# Nixie_Roehren-IN12b-V1_2.net
KiCad netlist of a schematic drawn in EAGLE
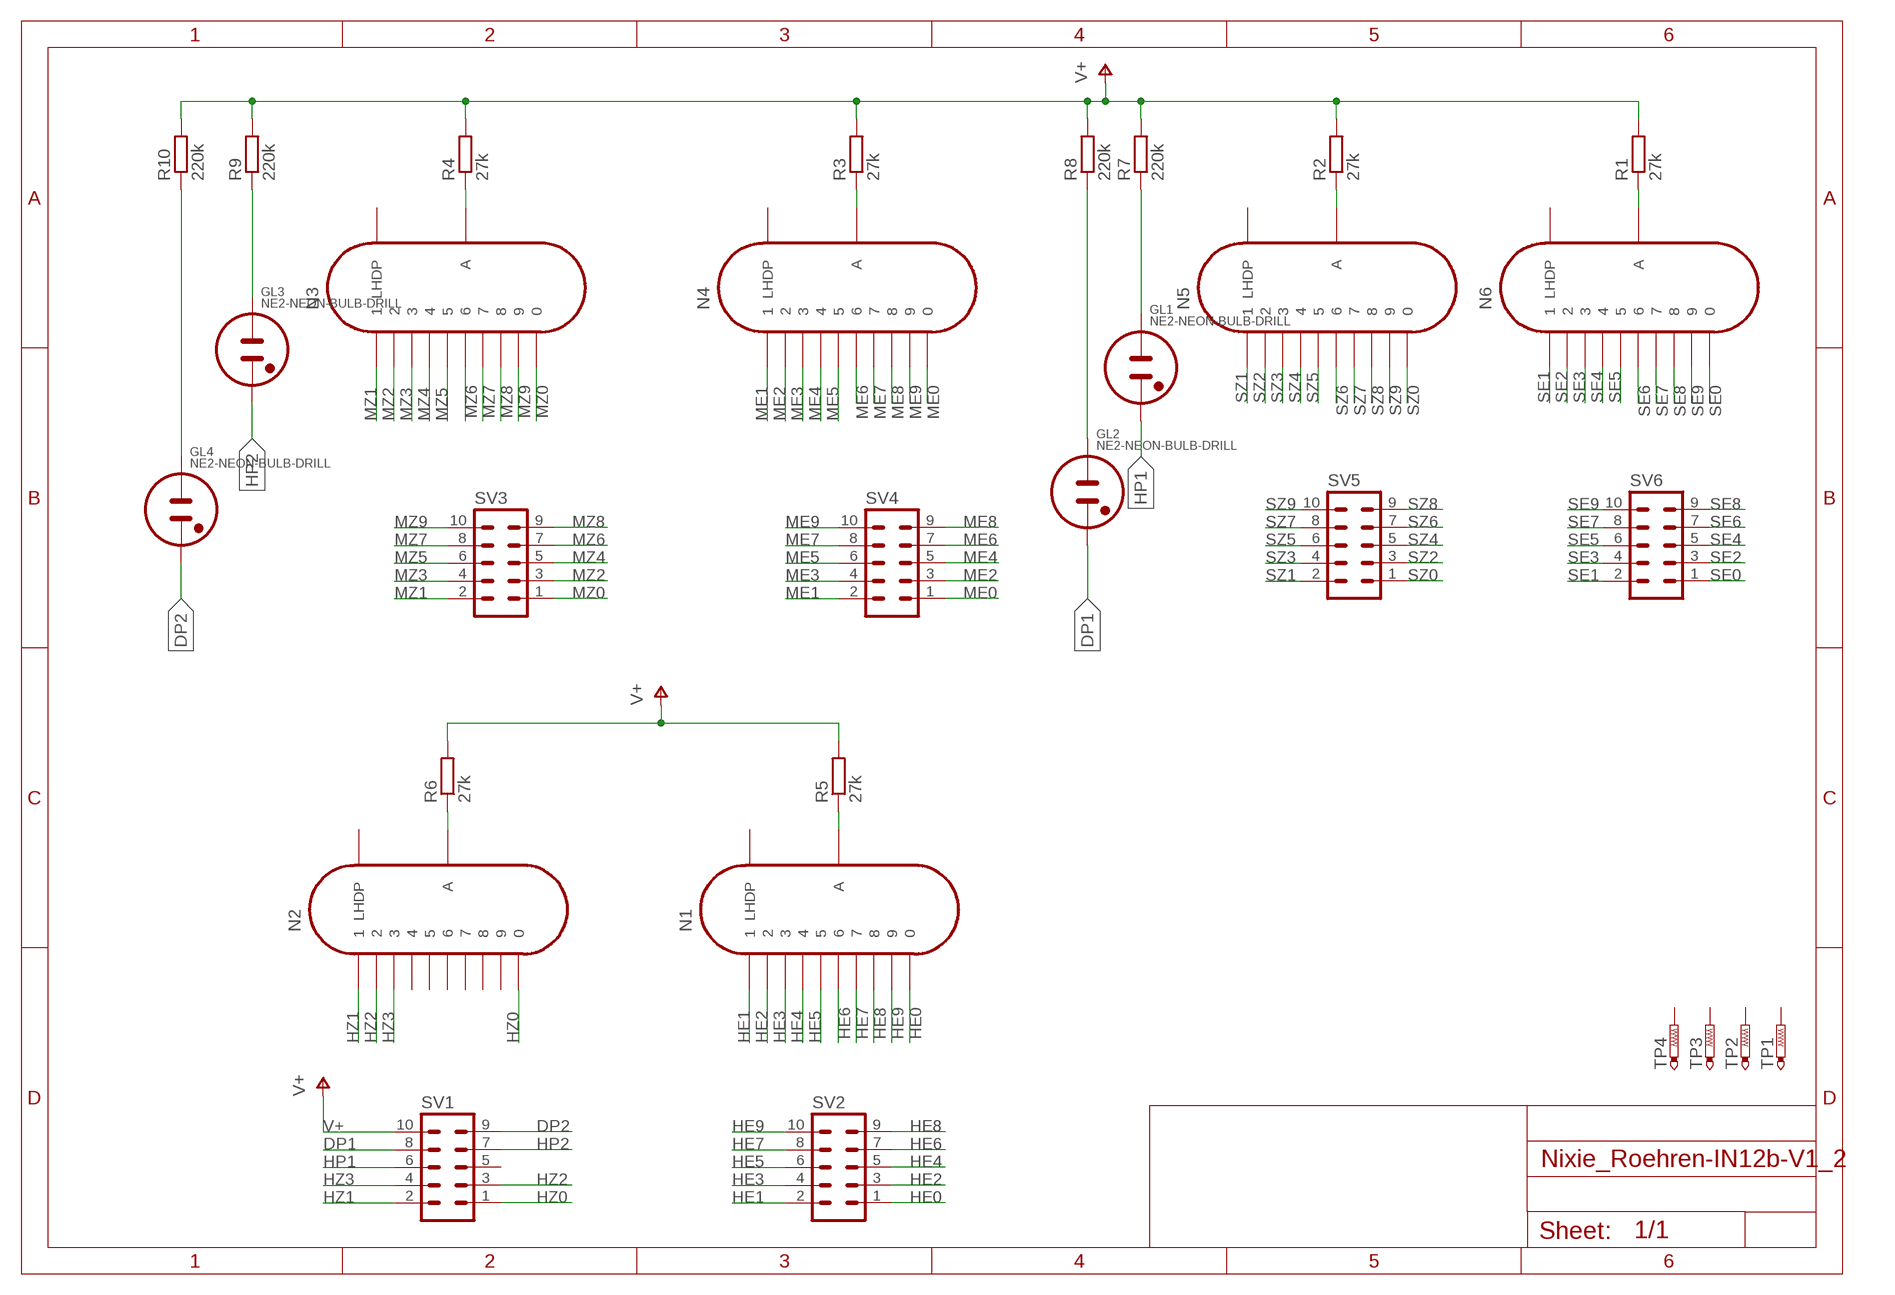
[diagram p0: schematic, sheet 1]

(export (version "E")
  (design (tool "Eeschema 10.0.6"))
  (components
    (comp (ref "GL1")
      (value "NE2-NEON-BULB-DRILL")
      (footprint "eagle-import:NE2-NEON-BULB-DRILL")
      (libsource (lib "eagle-import") (part "NE2-NEON-BULB-DRILL"))
    )
    (comp (ref "GL2")
      (value "NE2-NEON-BULB-DRILL")
      (footprint "eagle-import:NE2-NEON-BULB-DRILL")
      (libsource (lib "eagle-import") (part "NE2-NEON-BULB-DRILL"))
    )
    (comp (ref "GL3")
      (value "NE2-NEON-BULB-DRILL")
      (footprint "eagle-import:NE2-NEON-BULB-DRILL")
      (libsource (lib "eagle-import") (part "NE2-NEON-BULB-DRILL"))
    )
    (comp (ref "GL4")
      (value "NE2-NEON-BULB-DRILL")
      (footprint "eagle-import:NE2-NEON-BULB-DRILL")
      (libsource (lib "eagle-import") (part "NE2-NEON-BULB-DRILL"))
    )
    (comp (ref "N1")
      (value "IN-12B")
      (footprint "eagle-import:IN-12")
      (libsource (lib "eagle-import") (part "IN-12B"))
    )
    (comp (ref "N2")
      (value "IN-12B")
      (footprint "eagle-import:IN-12")
      (libsource (lib "eagle-import") (part "IN-12B"))
    )
    (comp (ref "N3")
      (value "IN-12B")
      (footprint "eagle-import:IN-12")
      (libsource (lib "eagle-import") (part "IN-12B"))
    )
    (comp (ref "N4")
      (value "IN-12B")
      (footprint "eagle-import:IN-12")
      (libsource (lib "eagle-import") (part "IN-12B"))
    )
    (comp (ref "N5")
      (value "IN-12B")
      (footprint "eagle-import:IN-12")
      (libsource (lib "eagle-import") (part "IN-12B"))
    )
    (comp (ref "N6")
      (value "IN-12B")
      (footprint "eagle-import:IN-12")
      (libsource (lib "eagle-import") (part "IN-12B"))
    )
    (comp (ref "R1")
      (value "27k")
      (footprint "eagle-import:0207_10")
      (libsource (lib "eagle-import") (part "R-EU_0207/10"))
    )
    (comp (ref "R2")
      (value "27k")
      (footprint "eagle-import:0207_10")
      (libsource (lib "eagle-import") (part "R-EU_0207/10"))
    )
    (comp (ref "R3")
      (value "27k")
      (footprint "eagle-import:0207_10")
      (libsource (lib "eagle-import") (part "R-EU_0207/10"))
    )
    (comp (ref "R4")
      (value "27k")
      (footprint "eagle-import:0207_10")
      (libsource (lib "eagle-import") (part "R-EU_0207/10"))
    )
    (comp (ref "R5")
      (value "27k")
      (footprint "eagle-import:0207_10")
      (libsource (lib "eagle-import") (part "R-EU_0207/10"))
    )
    (comp (ref "R6")
      (value "27k")
      (footprint "eagle-import:0207_10")
      (libsource (lib "eagle-import") (part "R-EU_0207/10"))
    )
    (comp (ref "R7")
      (value "220k")
      (footprint "eagle-import:0207_10")
      (libsource (lib "eagle-import") (part "R-EU_0207/10"))
    )
    (comp (ref "R8")
      (value "220k")
      (footprint "eagle-import:0207_10")
      (libsource (lib "eagle-import") (part "R-EU_0207/10"))
    )
    (comp (ref "R9")
      (value "220k")
      (footprint "eagle-import:0207_10")
      (libsource (lib "eagle-import") (part "R-EU_0207/10"))
    )
    (comp (ref "R10")
      (value "220k")
      (footprint "eagle-import:0207_10")
      (libsource (lib "eagle-import") (part "R-EU_0207/10"))
    )
    (comp (ref "SV1")
      (value "ML10")
      (footprint "eagle-import:ML10")
      (libsource (lib "eagle-import") (part "ML10"))
    )
    (comp (ref "SV2")
      (value "ML10")
      (footprint "eagle-import:ML10")
      (libsource (lib "eagle-import") (part "ML10"))
    )
    (comp (ref "SV3")
      (value "ML10")
      (footprint "eagle-import:ML10")
      (libsource (lib "eagle-import") (part "ML10"))
    )
    (comp (ref "SV4")
      (value "ML10")
      (footprint "eagle-import:ML10")
      (libsource (lib "eagle-import") (part "ML10"))
    )
    (comp (ref "SV5")
      (value "ML10")
      (footprint "eagle-import:ML10")
      (libsource (lib "eagle-import") (part "ML10"))
    )
    (comp (ref "SV6")
      (value "ML10")
      (footprint "eagle-import:ML10")
      (libsource (lib "eagle-import") (part "ML10"))
    )
    (comp (ref "TP1")
      (value "PTR1B1,27")
      (footprint "eagle-import:B1,27")
      (libsource (lib "eagle-import") (part "PTR1B1,27"))
    )
    (comp (ref "TP2")
      (value "PTR1B1,27")
      (footprint "eagle-import:B1,27")
      (libsource (lib "eagle-import") (part "PTR1B1,27"))
    )
    (comp (ref "TP3")
      (value "PTR1B1,27")
      (footprint "eagle-import:B1,27")
      (libsource (lib "eagle-import") (part "PTR1B1,27"))
    )
    (comp (ref "TP4")
      (value "PTR1B1,27")
      (footprint "eagle-import:B1,27")
      (libsource (lib "eagle-import") (part "PTR1B1,27"))
    )
  )
  (nets
    (net (code "1") (name "/HE0") (class "Default")
      (node (ref "N1") (pin "0") (pinfunction "0_0") (pintype "bidirectional"))
      (node (ref "SV2") (pin "1") (pinfunction "1_1") (pintype "passive"))
    )
    (net (code "2") (name "/HE1") (class "Default")
      (node (ref "N1") (pin "1") (pinfunction "1_1") (pintype "bidirectional"))
      (node (ref "SV2") (pin "2") (pinfunction "2_2") (pintype "passive"))
    )
    (net (code "3") (name "/HE2") (class "Default")
      (node (ref "N1") (pin "2") (pinfunction "2_2") (pintype "bidirectional"))
      (node (ref "SV2") (pin "3") (pinfunction "3_3") (pintype "passive"))
    )
    (net (code "4") (name "/HE3") (class "Default")
      (node (ref "N1") (pin "3") (pinfunction "3_3") (pintype "bidirectional"))
      (node (ref "SV2") (pin "4") (pinfunction "4_4") (pintype "passive"))
    )
    (net (code "5") (name "/HE4") (class "Default")
      (node (ref "N1") (pin "4") (pinfunction "4_4") (pintype "bidirectional"))
      (node (ref "SV2") (pin "5") (pinfunction "5_5") (pintype "passive"))
    )
    (net (code "6") (name "/HE5") (class "Default")
      (node (ref "N1") (pin "5") (pinfunction "5_5") (pintype "bidirectional"))
      (node (ref "SV2") (pin "6") (pinfunction "6_6") (pintype "passive"))
    )
    (net (code "7") (name "/HE6") (class "Default")
      (node (ref "N1") (pin "6") (pinfunction "6_6") (pintype "bidirectional"))
      (node (ref "SV2") (pin "7") (pinfunction "7_7") (pintype "passive"))
    )
    (net (code "8") (name "/HE7") (class "Default")
      (node (ref "N1") (pin "7") (pinfunction "7_7") (pintype "bidirectional"))
      (node (ref "SV2") (pin "8") (pinfunction "8_8") (pintype "passive"))
    )
    (net (code "9") (name "/HE8") (class "Default")
      (node (ref "N1") (pin "8") (pinfunction "8_8") (pintype "bidirectional"))
      (node (ref "SV2") (pin "9") (pinfunction "9_9") (pintype "passive"))
    )
    (net (code "10") (name "/HE9") (class "Default")
      (node (ref "N1") (pin "9") (pinfunction "9_9") (pintype "bidirectional"))
      (node (ref "SV2") (pin "10") (pinfunction "10_10") (pintype "passive"))
    )
    (net (code "11") (name "/HZ0") (class "Default")
      (node (ref "N2") (pin "0") (pinfunction "0_0") (pintype "bidirectional"))
      (node (ref "SV1") (pin "1") (pinfunction "1_1") (pintype "passive"))
    )
    (net (code "12") (name "/HZ1") (class "Default")
      (node (ref "N2") (pin "1") (pinfunction "1_1") (pintype "bidirectional"))
      (node (ref "SV1") (pin "2") (pinfunction "2_2") (pintype "passive"))
    )
    (net (code "13") (name "/HZ2") (class "Default")
      (node (ref "N2") (pin "2") (pinfunction "2_2") (pintype "bidirectional"))
      (node (ref "SV1") (pin "3") (pinfunction "3_3") (pintype "passive"))
    )
    (net (code "14") (name "/HZ3") (class "Default")
      (node (ref "N2") (pin "3") (pinfunction "3_3") (pintype "bidirectional"))
      (node (ref "SV1") (pin "4") (pinfunction "4_4") (pintype "passive"))
    )
    (net (code "15") (name "/ME0") (class "Default")
      (node (ref "N4") (pin "0") (pinfunction "0_0") (pintype "bidirectional"))
      (node (ref "SV4") (pin "1") (pinfunction "1_1") (pintype "passive"))
    )
    (net (code "16") (name "/ME1") (class "Default")
      (node (ref "N4") (pin "1") (pinfunction "1_1") (pintype "bidirectional"))
      (node (ref "SV4") (pin "2") (pinfunction "2_2") (pintype "passive"))
    )
    (net (code "17") (name "/ME2") (class "Default")
      (node (ref "N4") (pin "2") (pinfunction "2_2") (pintype "bidirectional"))
      (node (ref "SV4") (pin "3") (pinfunction "3_3") (pintype "passive"))
    )
    (net (code "18") (name "/ME3") (class "Default")
      (node (ref "N4") (pin "3") (pinfunction "3_3") (pintype "bidirectional"))
      (node (ref "SV4") (pin "4") (pinfunction "4_4") (pintype "passive"))
    )
    (net (code "19") (name "/ME4") (class "Default")
      (node (ref "N4") (pin "4") (pinfunction "4_4") (pintype "bidirectional"))
      (node (ref "SV4") (pin "5") (pinfunction "5_5") (pintype "passive"))
    )
    (net (code "20") (name "/ME5") (class "Default")
      (node (ref "N4") (pin "5") (pinfunction "5_5") (pintype "bidirectional"))
      (node (ref "SV4") (pin "6") (pinfunction "6_6") (pintype "passive"))
    )
    (net (code "21") (name "/ME6") (class "Default")
      (node (ref "N4") (pin "6") (pinfunction "6_6") (pintype "bidirectional"))
      (node (ref "SV4") (pin "7") (pinfunction "7_7") (pintype "passive"))
    )
    (net (code "22") (name "/ME7") (class "Default")
      (node (ref "N4") (pin "7") (pinfunction "7_7") (pintype "bidirectional"))
      (node (ref "SV4") (pin "8") (pinfunction "8_8") (pintype "passive"))
    )
    (net (code "23") (name "/ME8") (class "Default")
      (node (ref "N4") (pin "8") (pinfunction "8_8") (pintype "bidirectional"))
      (node (ref "SV4") (pin "9") (pinfunction "9_9") (pintype "passive"))
    )
    (net (code "24") (name "/ME9") (class "Default")
      (node (ref "N4") (pin "9") (pinfunction "9_9") (pintype "bidirectional"))
      (node (ref "SV4") (pin "10") (pinfunction "10_10") (pintype "passive"))
    )
    (net (code "25") (name "/MZ0") (class "Default")
      (node (ref "N3") (pin "0") (pinfunction "0_0") (pintype "bidirectional"))
      (node (ref "SV3") (pin "1") (pinfunction "1_1") (pintype "passive"))
    )
    (net (code "26") (name "/MZ1") (class "Default")
      (node (ref "N3") (pin "1") (pinfunction "1_1") (pintype "bidirectional"))
      (node (ref "SV3") (pin "2") (pinfunction "2_2") (pintype "passive"))
    )
    (net (code "27") (name "/MZ2") (class "Default")
      (node (ref "N3") (pin "2") (pinfunction "2_2") (pintype "bidirectional"))
      (node (ref "SV3") (pin "3") (pinfunction "3_3") (pintype "passive"))
    )
    (net (code "28") (name "/MZ3") (class "Default")
      (node (ref "N3") (pin "3") (pinfunction "3_3") (pintype "bidirectional"))
      (node (ref "SV3") (pin "4") (pinfunction "4_4") (pintype "passive"))
    )
    (net (code "29") (name "/MZ4") (class "Default")
      (node (ref "N3") (pin "4") (pinfunction "4_4") (pintype "bidirectional"))
      (node (ref "SV3") (pin "5") (pinfunction "5_5") (pintype "passive"))
    )
    (net (code "30") (name "/MZ5") (class "Default")
      (node (ref "N3") (pin "5") (pinfunction "5_5") (pintype "bidirectional"))
      (node (ref "SV3") (pin "6") (pinfunction "6_6") (pintype "passive"))
    )
    (net (code "31") (name "/MZ6") (class "Default")
      (node (ref "N3") (pin "6") (pinfunction "6_6") (pintype "bidirectional"))
      (node (ref "SV3") (pin "7") (pinfunction "7_7") (pintype "passive"))
    )
    (net (code "32") (name "/MZ7") (class "Default")
      (node (ref "N3") (pin "7") (pinfunction "7_7") (pintype "bidirectional"))
      (node (ref "SV3") (pin "8") (pinfunction "8_8") (pintype "passive"))
    )
    (net (code "33") (name "/MZ8") (class "Default")
      (node (ref "N3") (pin "8") (pinfunction "8_8") (pintype "bidirectional"))
      (node (ref "SV3") (pin "9") (pinfunction "9_9") (pintype "passive"))
    )
    (net (code "34") (name "/MZ9") (class "Default")
      (node (ref "N3") (pin "9") (pinfunction "9_9") (pintype "bidirectional"))
      (node (ref "SV3") (pin "10") (pinfunction "10_10") (pintype "passive"))
    )
    (net (code "35") (name "/SE0") (class "Default")
      (node (ref "N6") (pin "0") (pinfunction "0_0") (pintype "bidirectional"))
      (node (ref "SV6") (pin "1") (pinfunction "1_1") (pintype "passive"))
    )
    (net (code "36") (name "/SE1") (class "Default")
      (node (ref "N6") (pin "1") (pinfunction "1_1") (pintype "bidirectional"))
      (node (ref "SV6") (pin "2") (pinfunction "2_2") (pintype "passive"))
    )
    (net (code "37") (name "/SE2") (class "Default")
      (node (ref "N6") (pin "2") (pinfunction "2_2") (pintype "bidirectional"))
      (node (ref "SV6") (pin "3") (pinfunction "3_3") (pintype "passive"))
    )
    (net (code "38") (name "/SE3") (class "Default")
      (node (ref "N6") (pin "3") (pinfunction "3_3") (pintype "bidirectional"))
      (node (ref "SV6") (pin "4") (pinfunction "4_4") (pintype "passive"))
    )
    (net (code "39") (name "/SE4") (class "Default")
      (node (ref "N6") (pin "4") (pinfunction "4_4") (pintype "bidirectional"))
      (node (ref "SV6") (pin "5") (pinfunction "5_5") (pintype "passive"))
    )
    (net (code "40") (name "/SE5") (class "Default")
      (node (ref "N6") (pin "5") (pinfunction "5_5") (pintype "bidirectional"))
      (node (ref "SV6") (pin "6") (pinfunction "6_6") (pintype "passive"))
    )
    (net (code "41") (name "/SE6") (class "Default")
      (node (ref "N6") (pin "6") (pinfunction "6_6") (pintype "bidirectional"))
      (node (ref "SV6") (pin "7") (pinfunction "7_7") (pintype "passive"))
    )
    (net (code "42") (name "/SE7") (class "Default")
      (node (ref "N6") (pin "7") (pinfunction "7_7") (pintype "bidirectional"))
      (node (ref "SV6") (pin "8") (pinfunction "8_8") (pintype "passive"))
    )
    (net (code "43") (name "/SE8") (class "Default")
      (node (ref "N6") (pin "8") (pinfunction "8_8") (pintype "bidirectional"))
      (node (ref "SV6") (pin "9") (pinfunction "9_9") (pintype "passive"))
    )
    (net (code "44") (name "/SE9") (class "Default")
      (node (ref "N6") (pin "9") (pinfunction "9_9") (pintype "bidirectional"))
      (node (ref "SV6") (pin "10") (pinfunction "10_10") (pintype "passive"))
    )
    (net (code "45") (name "/SZ0") (class "Default")
      (node (ref "N5") (pin "0") (pinfunction "0_0") (pintype "bidirectional"))
      (node (ref "SV5") (pin "1") (pinfunction "1_1") (pintype "passive"))
    )
    (net (code "46") (name "/SZ1") (class "Default")
      (node (ref "N5") (pin "1") (pinfunction "1_1") (pintype "bidirectional"))
      (node (ref "SV5") (pin "2") (pinfunction "2_2") (pintype "passive"))
    )
    (net (code "47") (name "/SZ2") (class "Default")
      (node (ref "N5") (pin "2") (pinfunction "2_2") (pintype "bidirectional"))
      (node (ref "SV5") (pin "3") (pinfunction "3_3") (pintype "passive"))
    )
    (net (code "48") (name "/SZ3") (class "Default")
      (node (ref "N5") (pin "3") (pinfunction "3_3") (pintype "bidirectional"))
      (node (ref "SV5") (pin "4") (pinfunction "4_4") (pintype "passive"))
    )
    (net (code "49") (name "/SZ4") (class "Default")
      (node (ref "N5") (pin "4") (pinfunction "4_4") (pintype "bidirectional"))
      (node (ref "SV5") (pin "5") (pinfunction "5_5") (pintype "passive"))
    )
    (net (code "50") (name "/SZ5") (class "Default")
      (node (ref "N5") (pin "5") (pinfunction "5_5") (pintype "bidirectional"))
      (node (ref "SV5") (pin "6") (pinfunction "6_6") (pintype "passive"))
    )
    (net (code "51") (name "/SZ6") (class "Default")
      (node (ref "N5") (pin "6") (pinfunction "6_6") (pintype "bidirectional"))
      (node (ref "SV5") (pin "7") (pinfunction "7_7") (pintype "passive"))
    )
    (net (code "52") (name "/SZ7") (class "Default")
      (node (ref "N5") (pin "7") (pinfunction "7_7") (pintype "bidirectional"))
      (node (ref "SV5") (pin "8") (pinfunction "8_8") (pintype "passive"))
    )
    (net (code "53") (name "/SZ8") (class "Default")
      (node (ref "N5") (pin "8") (pinfunction "8_8") (pintype "bidirectional"))
      (node (ref "SV5") (pin "9") (pinfunction "9_9") (pintype "passive"))
    )
    (net (code "54") (name "/SZ9") (class "Default")
      (node (ref "N5") (pin "9") (pinfunction "9_9") (pintype "bidirectional"))
      (node (ref "SV5") (pin "10") (pinfunction "10_10") (pintype "passive"))
    )
    (net (code "55") (name "DP1") (class "Default")
      (node (ref "GL2") (pin "2") (pinfunction "A1_2") (pintype "passive"))
      (node (ref "SV1") (pin "8") (pinfunction "8_8") (pintype "passive"))
    )
    (net (code "56") (name "DP2") (class "Default")
      (node (ref "GL4") (pin "2") (pinfunction "A1_2") (pintype "passive"))
      (node (ref "SV1") (pin "9") (pinfunction "9_9") (pintype "passive"))
    )
    (net (code "57") (name "HP1") (class "Default")
      (node (ref "GL1") (pin "2") (pinfunction "A1_2") (pintype "passive"))
      (node (ref "SV1") (pin "6") (pinfunction "6_6") (pintype "passive"))
    )
    (net (code "58") (name "HP2") (class "Default")
      (node (ref "GL3") (pin "2") (pinfunction "A1_2") (pintype "passive"))
      (node (ref "SV1") (pin "7") (pinfunction "7_7") (pintype "passive"))
    )
    (net (code "59") (name "Net-(GL1-A)") (class "Default")
      (node (ref "GL1") (pin "1") (pinfunction "A_1") (pintype "passive"))
      (node (ref "R7") (pin "1") (pinfunction "1_1") (pintype "passive"))
    )
    (net (code "60") (name "Net-(GL2-A)") (class "Default")
      (node (ref "GL2") (pin "1") (pinfunction "A_1") (pintype "passive"))
      (node (ref "R8") (pin "1") (pinfunction "1_1") (pintype "passive"))
    )
    (net (code "61") (name "Net-(GL3-A)") (class "Default")
      (node (ref "GL3") (pin "1") (pinfunction "A_1") (pintype "passive"))
      (node (ref "R9") (pin "1") (pinfunction "1_1") (pintype "passive"))
    )
    (net (code "62") (name "Net-(GL4-A)") (class "Default")
      (node (ref "GL4") (pin "1") (pinfunction "A_1") (pintype "passive"))
      (node (ref "R10") (pin "1") (pinfunction "1_1") (pintype "passive"))
    )
    (net (code "63") (name "Net-(N1-PadA)") (class "Default")
      (node (ref "N1") (pin "A") (pinfunction "A_A") (pintype "bidirectional"))
      (node (ref "R5") (pin "1") (pinfunction "1_1") (pintype "passive"))
    )
    (net (code "64") (name "Net-(N2-PadA)") (class "Default")
      (node (ref "N2") (pin "A") (pinfunction "A_A") (pintype "bidirectional"))
      (node (ref "R6") (pin "1") (pinfunction "1_1") (pintype "passive"))
    )
    (net (code "65") (name "Net-(N3-PadA)") (class "Default")
      (node (ref "N3") (pin "A") (pinfunction "A_A") (pintype "bidirectional"))
      (node (ref "R4") (pin "1") (pinfunction "1_1") (pintype "passive"))
    )
    (net (code "66") (name "Net-(N4-PadA)") (class "Default")
      (node (ref "N4") (pin "A") (pinfunction "A_A") (pintype "bidirectional"))
      (node (ref "R3") (pin "1") (pinfunction "1_1") (pintype "passive"))
    )
    (net (code "67") (name "Net-(N5-PadA)") (class "Default")
      (node (ref "N5") (pin "A") (pinfunction "A_A") (pintype "bidirectional"))
      (node (ref "R2") (pin "1") (pinfunction "1_1") (pintype "passive"))
    )
    (net (code "68") (name "Net-(N6-PadA)") (class "Default")
      (node (ref "N6") (pin "A") (pinfunction "A_A") (pintype "bidirectional"))
      (node (ref "R1") (pin "1") (pinfunction "1_1") (pintype "passive"))
    )
    (net (code "69") (name "V+") (class "Default")
      (node (ref "R1") (pin "2") (pinfunction "2_2") (pintype "passive"))
      (node (ref "R10") (pin "2") (pinfunction "2_2") (pintype "passive"))
      (node (ref "R2") (pin "2") (pinfunction "2_2") (pintype "passive"))
      (node (ref "R3") (pin "2") (pinfunction "2_2") (pintype "passive"))
      (node (ref "R4") (pin "2") (pinfunction "2_2") (pintype "passive"))
      (node (ref "R5") (pin "2") (pinfunction "2_2") (pintype "passive"))
      (node (ref "R6") (pin "2") (pinfunction "2_2") (pintype "passive"))
      (node (ref "R7") (pin "2") (pinfunction "2_2") (pintype "passive"))
      (node (ref "R8") (pin "2") (pinfunction "2_2") (pintype "passive"))
      (node (ref "R9") (pin "2") (pinfunction "2_2") (pintype "passive"))
      (node (ref "SV1") (pin "10") (pinfunction "10_10") (pintype "passive"))
    )
    (net (code "70") (name "unconnected-(N1-PadLHDP)") (class "Default")
      (node (ref "N1") (pin "LHDP") (pinfunction "LHDP_LHDP") (pintype "bidirectional"))
    )
    (net (code "71") (name "unconnected-(N2-Pad4)") (class "Default")
      (node (ref "N2") (pin "4") (pinfunction "4_4") (pintype "bidirectional"))
    )
    (net (code "72") (name "unconnected-(N2-Pad5)") (class "Default")
      (node (ref "N2") (pin "5") (pinfunction "5_5") (pintype "bidirectional"))
    )
    (net (code "73") (name "unconnected-(N2-Pad6)") (class "Default")
      (node (ref "N2") (pin "6") (pinfunction "6_6") (pintype "bidirectional"))
    )
    (net (code "74") (name "unconnected-(N2-Pad7)") (class "Default")
      (node (ref "N2") (pin "7") (pinfunction "7_7") (pintype "bidirectional"))
    )
    (net (code "75") (name "unconnected-(N2-Pad8)") (class "Default")
      (node (ref "N2") (pin "8") (pinfunction "8_8") (pintype "bidirectional"))
    )
    (net (code "76") (name "unconnected-(N2-Pad9)") (class "Default")
      (node (ref "N2") (pin "9") (pinfunction "9_9") (pintype "bidirectional"))
    )
    (net (code "77") (name "unconnected-(N2-PadLHDP)") (class "Default")
      (node (ref "N2") (pin "LHDP") (pinfunction "LHDP_LHDP") (pintype "bidirectional"))
    )
    (net (code "78") (name "unconnected-(N3-PadLHDP)") (class "Default")
      (node (ref "N3") (pin "LHDP") (pinfunction "LHDP_LHDP") (pintype "bidirectional"))
    )
    (net (code "79") (name "unconnected-(N4-PadLHDP)") (class "Default")
      (node (ref "N4") (pin "LHDP") (pinfunction "LHDP_LHDP") (pintype "bidirectional"))
    )
    (net (code "80") (name "unconnected-(N5-PadLHDP)") (class "Default")
      (node (ref "N5") (pin "LHDP") (pinfunction "LHDP_LHDP") (pintype "bidirectional"))
    )
    (net (code "81") (name "unconnected-(N6-PadLHDP)") (class "Default")
      (node (ref "N6") (pin "LHDP") (pinfunction "LHDP_LHDP") (pintype "bidirectional"))
    )
    (net (code "82") (name "unconnected-(SV1-Pad5)") (class "Default")
      (node (ref "SV1") (pin "5") (pinfunction "5_5") (pintype "passive"))
    )
    (net (code "83") (name "unconnected-(TP1-PadTP)") (class "Default")
      (node (ref "TP1") (pin "TP") (pinfunction "TP_TP") (pintype "input"))
    )
    (net (code "84") (name "unconnected-(TP2-PadTP)") (class "Default")
      (node (ref "TP2") (pin "TP") (pinfunction "TP_TP") (pintype "input"))
    )
    (net (code "85") (name "unconnected-(TP3-PadTP)") (class "Default")
      (node (ref "TP3") (pin "TP") (pinfunction "TP_TP") (pintype "input"))
    )
    (net (code "86") (name "unconnected-(TP4-PadTP)") (class "Default")
      (node (ref "TP4") (pin "TP") (pinfunction "TP_TP") (pintype "input"))
    )
  )
)
